# Sheet1.net
KiCad netlist of a schematic drawn in Altium Designer
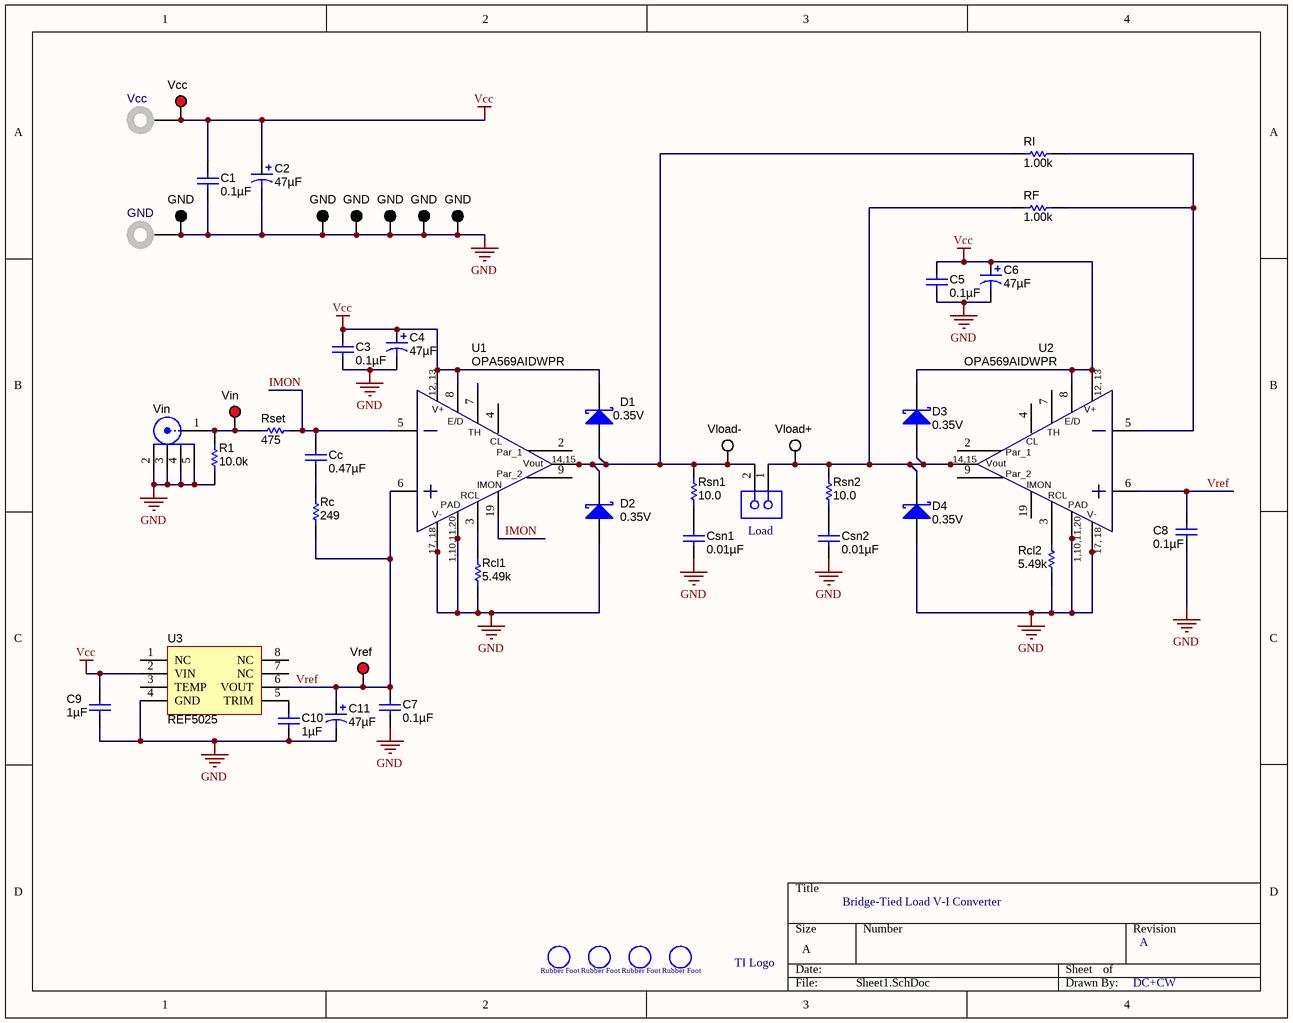
[diagram p0: Sheet1.SchDoc]

(export (version "E")
  (design (tool "Eeschema 10.0.6"))
  (components
    (comp (ref "C1")
      (value "12065C104JAT2A")
      (footprint "1206")
      (description "CAP, CERM, 0.1uF, 50V, +/-5%, X7R, 1206")
      (fields
        (field (name "VALUEDISPLAYED") "0.1µF")
        (field (name "MANUFACTURER") "AVX")
        (field (name "PUBLISHER") "Texas Instruments")
      )
      (libsource (lib "Capacitor_Ceramic") (part "12065C104JAT2A"))
    )
    (comp (ref "C2")
      (value "293D476X0016D2TE3")
      (footprint "7343-31")
      (description "CAP, TANT, 47uF, 16V, +/-20%, 0.7 ohm, 7343-31 SMD")
      (fields
        (field (name "VALUEDISPLAYED") "47µF")
        (field (name "MANUFACTURER") "Vishay-Sprague")
        (field (name "PUBLISHER") "Texas Instruments")
      )
      (libsource (lib "Capacitor_Tantalum") (part "293D476X0016D2TE3"))
    )
    (comp (ref "C3")
      (value "12065C104JAT2A")
      (footprint "1206")
      (description "CAP, CERM, 0.1uF, 50V, +/-5%, X7R, 1206")
      (fields
        (field (name "VALUEDISPLAYED") "0.1µF")
        (field (name "MANUFACTURER") "AVX")
        (field (name "PUBLISHER") "Texas Instruments")
      )
      (libsource (lib "Capacitor_Ceramic") (part "12065C104JAT2A"))
    )
    (comp (ref "C4")
      (value "293D476X0016D2TE3")
      (footprint "7343-31")
      (description "CAP, TANT, 47uF, 16V, +/-20%, 0.7 ohm, 7343-31 SMD")
      (fields
        (field (name "VALUEDISPLAYED") "47µF")
        (field (name "MANUFACTURER") "Vishay-Sprague")
        (field (name "PUBLISHER") "Texas Instruments")
      )
      (libsource (lib "Capacitor_Tantalum") (part "293D476X0016D2TE3"))
    )
    (comp (ref "C5")
      (value "12065C104JAT2A")
      (footprint "1206")
      (description "CAP, CERM, 0.1uF, 50V, +/-5%, X7R, 1206")
      (fields
        (field (name "VALUEDISPLAYED") "0.1µF")
        (field (name "MANUFACTURER") "AVX")
        (field (name "PUBLISHER") "Texas Instruments")
      )
      (libsource (lib "Capacitor_Ceramic") (part "12065C104JAT2A"))
    )
    (comp (ref "C6")
      (value "293D476X0016D2TE3")
      (footprint "7343-31")
      (description "CAP, TANT, 47uF, 16V, +/-20%, 0.7 ohm, 7343-31 SMD")
      (fields
        (field (name "VALUEDISPLAYED") "47µF")
        (field (name "MANUFACTURER") "Vishay-Sprague")
        (field (name "PUBLISHER") "Texas Instruments")
      )
      (libsource (lib "Capacitor_Tantalum") (part "293D476X0016D2TE3"))
    )
    (comp (ref "C7")
      (value "12065C104JAT2A")
      (footprint "1206")
      (description "CAP, CERM, 0.1uF, 50V, +/-5%, X7R, 1206")
      (fields
        (field (name "VALUEDISPLAYED") "0.1µF")
        (field (name "MANUFACTURER") "AVX")
        (field (name "PUBLISHER") "Texas Instruments")
      )
      (libsource (lib "Capacitor_Ceramic") (part "12065C104JAT2A"))
    )
    (comp (ref "C8")
      (value "12065C104JAT2A")
      (footprint "1206")
      (description "CAP, CERM, 0.1uF, 50V, +/-5%, X7R, 1206")
      (fields
        (field (name "VALUEDISPLAYED") "0.1µF")
        (field (name "MANUFACTURER") "AVX")
        (field (name "PUBLISHER") "Texas Instruments")
      )
      (libsource (lib "Capacitor_Ceramic") (part "12065C104JAT2A"))
    )
    (comp (ref "C9")
      (value "GRM188R71E105KA12D")
      (footprint "0603")
      (description "CAP, CERM, 1uF, 25V, +/-10%, X7R, 0603")
      (fields
        (field (name "VALUEDISPLAYED") "1µF")
        (field (name "MANUFACTURER") "MuRata")
        (field (name "PUBLISHER") "Texas Instruments")
      )
      (libsource (lib "Capacitor_Ceramic") (part "GRM188R71E105KA12D"))
    )
    (comp (ref "C10")
      (value "GRM188R71E105KA12D")
      (footprint "0603")
      (description "CAP, CERM, 1uF, 25V, +/-10%, X7R, 0603")
      (fields
        (field (name "VALUEDISPLAYED") "1µF")
        (field (name "MANUFACTURER") "MuRata")
        (field (name "PUBLISHER") "Texas Instruments")
      )
      (libsource (lib "Capacitor_Ceramic") (part "GRM188R71E105KA12D"))
    )
    (comp (ref "C11")
      (value "293D476X0016D2TE3")
      (footprint "7343-31")
      (description "CAP, TANT, 47uF, 16V, +/-20%, 0.7 ohm, 7343-31 SMD")
      (fields
        (field (name "VALUEDISPLAYED") "47µF")
        (field (name "MANUFACTURER") "Vishay-Sprague")
        (field (name "PUBLISHER") "Texas Instruments")
      )
      (libsource (lib "Capacitor_Tantalum") (part "293D476X0016D2TE3"))
    )
    (comp (ref "Cc")
      (value "C3216X7R2A474K")
      (footprint "1206")
      (description "CAP, CERM, 0.47uF, 100V, +/-10%, X7R, 1206")
      (fields
        (field (name "VALUEDISPLAYED") "0.47µF")
        (field (name "MANUFACTURER") "TDK")
        (field (name "PUBLISHER") "Texas Instruments")
      )
      (libsource (lib "Capacitor_Ceramic") (part "C3216X7R2A474K"))
    )
    (comp (ref "Csn1")
      (value "C0603C103J5RACTU")
      (footprint "0603")
      (description "CAP, CERM, 0.01uF, 50V, +/-5%, X7R, 0603")
      (fields
        (field (name "VALUEDISPLAYED") "0.01µF")
        (field (name "MANUFACTURER") "Kemet")
        (field (name "PUBLISHER") "Texas Instruments")
      )
      (libsource (lib "Capacitor_Ceramic") (part "C0603C103J5RACTU"))
    )
    (comp (ref "Csn2")
      (value "C0603C103J5RACTU")
      (footprint "0603")
      (description "CAP, CERM, 0.01uF, 50V, +/-5%, X7R, 0603")
      (fields
        (field (name "VALUEDISPLAYED") "0.01µF")
        (field (name "MANUFACTURER") "Kemet")
        (field (name "PUBLISHER") "Texas Instruments")
      )
      (libsource (lib "Capacitor_Ceramic") (part "C0603C103J5RACTU"))
    )
    (comp (ref "D1")
      (value "0.35V")
      (footprint "SMC")
      (description "Diode, Schottky, 15V, 3A, SMC")
      (fields
        (field (name "PARTNUMBER") "30BQ015TRPBF")
        (field (name "MANUFACTURER") "International Rectifier")
        (field (name "PUBLISHER") "Texas Instruments")
      )
      (libsource (lib "Diode") (part "30BQ015TRPBF"))
    )
    (comp (ref "D2")
      (value "0.35V")
      (footprint "SMC")
      (description "Diode, Schottky, 15V, 3A, SMC")
      (fields
        (field (name "PARTNUMBER") "30BQ015TRPBF")
        (field (name "MANUFACTURER") "International Rectifier")
        (field (name "PUBLISHER") "Texas Instruments")
      )
      (libsource (lib "Diode") (part "30BQ015TRPBF"))
    )
    (comp (ref "D3")
      (value "0.35V")
      (footprint "SMC")
      (description "Diode, Schottky, 15V, 3A, SMC")
      (fields
        (field (name "PARTNUMBER") "30BQ015TRPBF")
        (field (name "MANUFACTURER") "International Rectifier")
        (field (name "PUBLISHER") "Texas Instruments")
      )
      (libsource (lib "Diode") (part "30BQ015TRPBF"))
    )
    (comp (ref "D4")
      (value "0.35V")
      (footprint "SMC")
      (description "Diode, Schottky, 15V, 3A, SMC")
      (fields
        (field (name "PARTNUMBER") "30BQ015TRPBF")
        (field (name "MANUFACTURER") "International Rectifier")
        (field (name "PUBLISHER") "Texas Instruments")
      )
      (libsource (lib "Diode") (part "30BQ015TRPBF"))
    )
    (comp (ref "F1")
      (value "~")
      (footprint "Rubber_Foot")
      (description "BUMPON CYLINDRICAL .312X.200 BLK")
      (fields (field (name "MANUFACTURER") "3M") (field (name "SYMBOLCREATOR") "use LDAP id"))
      (libsource (lib "Schlib1") (part "SJ61A1"))
    )
    (comp (ref "F2")
      (value "~")
      (footprint "Rubber_Foot")
      (description "BUMPON CYLINDRICAL .312X.200 BLK")
      (fields (field (name "MANUFACTURER") "3M") (field (name "SYMBOLCREATOR") "use LDAP id"))
      (libsource (lib "Schlib1") (part "SJ61A1"))
    )
    (comp (ref "F3")
      (value "~")
      (footprint "Rubber_Foot")
      (description "BUMPON CYLINDRICAL .312X.200 BLK")
      (fields (field (name "MANUFACTURER") "3M") (field (name "SYMBOLCREATOR") "use LDAP id"))
      (libsource (lib "Schlib1") (part "SJ61A1"))
    )
    (comp (ref "F4")
      (value "~")
      (footprint "Rubber_Foot")
      (description "BUMPON CYLINDRICAL .312X.200 BLK")
      (fields (field (name "MANUFACTURER") "3M") (field (name "SYMBOLCREATOR") "use LDAP id"))
      (libsource (lib "Schlib1") (part "SJ61A1"))
    )
    (comp (ref "GND")
      (value "~")
      (footprint "Keystone_575-4")
      (description "Standard Banana Jack, Uninsulated, 5.5mm")
      (fields
        (field (name "PARTNUMBER") "575-4")
        (field (name "MANUFACTURER") "Keystone")
        (field (name "PUBLISHER") "National Semiconductor")
      )
      (libsource (lib "Connectors") (part "575-4"))
    )
    (comp (ref "Load")
      (value "~")
      (footprint "PhoenixContact_1715721")
      (description "Conn Term Block, 2POS, 5.08mm PCB")
      (fields
        (field (name "PARTNUMBER") "1715721")
        (field (name "MANUFACTURER") "Phoenix Contact")
        (field (name "PUBLISHER") "National Semiconductor")
      )
      (libsource (lib "Connectors") (part "1715721"))
    )
    (comp (ref "R1")
      (value "10.0k")
      (footprint "0603")
      (description "RES, 10.0k ohm, 1%, 0.1W, 0603")
      (fields
        (field (name "PARTNUMBER") "RC0603FR-0710KL")
        (field (name "MANUFACTURER") "Yageo America")
        (field (name "PUBLISHER") "Texas Instruments")
      )
      (libsource (lib "Resistor_0603") (part "RC0603FR-0710KL"))
    )
    (comp (ref "Rc")
      (value "249")
      (footprint "0603")
      (description "RES, 249 ohm, 1%, 0.1W, 0603")
      (fields
        (field (name "PARTNUMBER") "RC0603FR-07249RL")
        (field (name "MANUFACTURER") "Yageo America")
        (field (name "PUBLISHER") "Texas Instruments")
      )
      (libsource (lib "Resistor_0603") (part "RC0603FR-07249RL"))
    )
    (comp (ref "Rcl1")
      (value "5.49k")
      (footprint "0603")
      (description "RES, 5.49k ohm, 1%, 0.1W, 0603")
      (fields
        (field (name "PARTNUMBER") "RC0603FR-075K49L")
        (field (name "MANUFACTURER") "Yageo America")
        (field (name "PUBLISHER") "Texas Instruments")
      )
      (libsource (lib "Resistor_0603") (part "RC0603FR-075K49L"))
    )
    (comp (ref "Rcl2")
      (value "5.49k")
      (footprint "0603")
      (description "RES, 5.49k ohm, 1%, 0.1W, 0603")
      (fields
        (field (name "PARTNUMBER") "RC0603FR-075K49L")
        (field (name "MANUFACTURER") "Yageo America")
        (field (name "PUBLISHER") "Texas Instruments")
      )
      (libsource (lib "Resistor_0603") (part "RC0603FR-075K49L"))
    )
    (comp (ref "RF")
      (value "1.00k")
      (footprint "0603")
      (description "RES, 1.00k ohm, 1%, 0.1W, 0603")
      (fields
        (field (name "PARTNUMBER") "RC0603FR-071KL")
        (field (name "MANUFACTURER") "Yageo America")
        (field (name "PUBLISHER") "Texas Instruments")
      )
      (libsource (lib "Resistor_0603") (part "RC0603FR-071KL"))
    )
    (comp (ref "RI")
      (value "1.00k")
      (footprint "0603")
      (description "RES, 1.00k ohm, 1%, 0.1W, 0603")
      (fields
        (field (name "PARTNUMBER") "RC0603FR-071KL")
        (field (name "MANUFACTURER") "Yageo America")
        (field (name "PUBLISHER") "Texas Instruments")
      )
      (libsource (lib "Resistor_0603") (part "RC0603FR-071KL"))
    )
    (comp (ref "Rset")
      (value "475")
      (footprint "0603")
      (description "RES, 475 ohm, 1%, 0.1W, 0603")
      (fields
        (field (name "PARTNUMBER") "RC0603FR-07475RL")
        (field (name "MANUFACTURER") "Yageo America")
        (field (name "PUBLISHER") "Texas Instruments")
      )
      (libsource (lib "Resistor_0603") (part "RC0603FR-07475RL"))
    )
    (comp (ref "Rsn1")
      (value "10.0")
      (footprint "0603")
      (description "RES, 10.0 ohm, 1%, 0.1W, 0603")
      (fields
        (field (name "PARTNUMBER") "CRCW060310R0FKEA")
        (field (name "MANUFACTURER") "Vishay-Dale")
        (field (name "PUBLISHER") "Texas Instruments")
      )
      (libsource (lib "Resistor_0603") (part "CRCW060310R0FKEA"))
    )
    (comp (ref "Rsn2")
      (value "10.0")
      (footprint "0603")
      (description "RES, 10.0 ohm, 1%, 0.1W, 0603")
      (fields
        (field (name "PARTNUMBER") "CRCW060310R0FKEA")
        (field (name "MANUFACTURER") "Vishay-Dale")
        (field (name "PUBLISHER") "Texas Instruments")
      )
      (libsource (lib "Resistor_0603") (part "CRCW060310R0FKEA"))
    )
    (comp (ref "TI1")
      (value "Texas Instruments logo")
      (footprint "TI LOGO")
      (description "TI BUG")
      (libsource (lib "Schlib1") (part "TI LOGO"))
    )
    (comp (ref "TP1")
      (value "Vcc")
      (footprint "Keystone5000")
      (description "Test Point, TH, Miniature, Red")
      (fields
        (field (name "MANUFACTURER") "Keystone")
        (field (name "DIGIKEYPARTNUMBER") "5000K-ND")
        (field (name "PUBLISHER") "National Semiconductor")
      )
      (libsource (lib "Connectors") (part "5000"))
    )
    (comp (ref "TP2")
      (value "GND")
      (footprint "Keystone5001")
      (description "Test Point, TH, Miniature, Black")
      (fields
        (field (name "MANUFACTURER") "Keystone")
        (field (name "DIGIKEYPARTNUMBER") "5001K-ND")
        (field (name "PUBLISHER") "National Semiconductor")
      )
      (libsource (lib "Connectors") (part "5001"))
    )
    (comp (ref "TP3")
      (value "GND")
      (footprint "Keystone5001")
      (description "Test Point, TH, Miniature, Black")
      (fields
        (field (name "MANUFACTURER") "Keystone")
        (field (name "DIGIKEYPARTNUMBER") "5001K-ND")
        (field (name "PUBLISHER") "National Semiconductor")
      )
      (libsource (lib "Connectors") (part "5001"))
    )
    (comp (ref "TP4")
      (value "GND")
      (footprint "Keystone5001")
      (description "Test Point, TH, Miniature, Black")
      (fields
        (field (name "MANUFACTURER") "Keystone")
        (field (name "DIGIKEYPARTNUMBER") "5001K-ND")
        (field (name "PUBLISHER") "National Semiconductor")
      )
      (libsource (lib "Connectors") (part "5001"))
    )
    (comp (ref "TP5")
      (value "GND")
      (footprint "Keystone5001")
      (description "Test Point, TH, Miniature, Black")
      (fields
        (field (name "MANUFACTURER") "Keystone")
        (field (name "DIGIKEYPARTNUMBER") "5001K-ND")
        (field (name "PUBLISHER") "National Semiconductor")
      )
      (libsource (lib "Connectors") (part "5001"))
    )
    (comp (ref "TP6")
      (value "GND")
      (footprint "Keystone5001")
      (description "Test Point, TH, Miniature, Black")
      (fields
        (field (name "MANUFACTURER") "Keystone")
        (field (name "DIGIKEYPARTNUMBER") "5001K-ND")
        (field (name "PUBLISHER") "National Semiconductor")
      )
      (libsource (lib "Connectors") (part "5001"))
    )
    (comp (ref "TP7")
      (value "GND")
      (footprint "Keystone5001")
      (description "Test Point, TH, Miniature, Black")
      (fields
        (field (name "MANUFACTURER") "Keystone")
        (field (name "DIGIKEYPARTNUMBER") "5001K-ND")
        (field (name "PUBLISHER") "National Semiconductor")
      )
      (libsource (lib "Connectors") (part "5001"))
    )
    (comp (ref "TP9")
      (value "Vin")
      (footprint "Keystone5000")
      (description "Test Point, TH, Miniature, Red")
      (fields
        (field (name "MANUFACTURER") "Keystone")
        (field (name "DIGIKEYPARTNUMBER") "5000K-ND")
        (field (name "PUBLISHER") "National Semiconductor")
      )
      (libsource (lib "Connectors") (part "5000"))
    )
    (comp (ref "TP10")
      (value "Vload-")
      (footprint "Keystone5002")
      (description "Test Point, TH, Miniature, White")
      (fields
        (field (name "MANUFACTURER") "Keystone")
        (field (name "DIGIKEYPARTNUMBER") "5002K-ND")
        (field (name "PUBLISHER") "National Semiconductor")
      )
      (libsource (lib "Connectors") (part "5002"))
    )
    (comp (ref "TP11")
      (value "Vload+")
      (footprint "Keystone5002")
      (description "Test Point, TH, Miniature, White")
      (fields
        (field (name "MANUFACTURER") "Keystone")
        (field (name "DIGIKEYPARTNUMBER") "5002K-ND")
        (field (name "PUBLISHER") "National Semiconductor")
      )
      (libsource (lib "Connectors") (part "5002"))
    )
    (comp (ref "TP13")
      (value "Vref")
      (footprint "Keystone5000")
      (description "Test Point, TH, Miniature, Red")
      (fields
        (field (name "MANUFACTURER") "Keystone")
        (field (name "DIGIKEYPARTNUMBER") "5000K-ND")
        (field (name "PUBLISHER") "National Semiconductor")
      )
      (libsource (lib "Connectors") (part "5000"))
    )
    (comp (ref "U1")
      (value "OPA569AIDWPR")
      (footprint "SOIC-20-PWP (DWP)")
      (description "IC OPAMP GP R-R 1.2MHZ 20SOIC")
      (fields (field (name "MANUFACTURER") "Texas Instruments") (field (name "SYMBOLCREATOR") "Use LDAP id"))
      (libsource (lib "Schlib1") (part "OPA569"))
    )
    (comp (ref "U2")
      (value "OPA569AIDWPR")
      (footprint "SOIC-20-PWP (DWP)")
      (description "IC OPAMP GP R-R 1.2MHZ 20SOIC")
      (fields (field (name "MANUFACTURER") "Texas Instruments") (field (name "SYMBOLCREATOR") "Use LDAP id"))
      (libsource (lib "Schlib1") (part "OPA569"))
    )
    (comp (ref "U3")
      (value "REF5025")
      (footprint "M08A_M")
      (description "IC VREF SERIES PREC 2.5V 8-SOIC")
      (fields
        (field (name "MANUFACTURER") "Texas Instruments")
        (field (name "PARTNUMBER") "8-SOIC")
        (field (name "SYMBOLCREATOR") "Use LDAP id")
      )
      (libsource (lib "Schlib1") (part "REF5025"))
    )
    (comp (ref "Vcc")
      (value "~")
      (footprint "Keystone_575-4")
      (description "Standard Banana Jack, Uninsulated, 5.5mm")
      (fields
        (field (name "PARTNUMBER") "575-4")
        (field (name "MANUFACTURER") "Keystone")
        (field (name "PUBLISHER") "National Semiconductor")
      )
      (libsource (lib "Connectors") (part "575-4"))
    )
    (comp (ref "Vin")
      (value "~")
      (footprint "Johnson_142-0701-20x")
      (description "Connector, TH, SMA")
      (fields
        (field (name "PARTNUMBER") "142-0701-201")
        (field (name "MANUFACTURER") "Emerson Network Power")
        (field (name "PUBLISHER") "National Semiconductor")
      )
      (libsource (lib "Connectors") (part "142-0701-201"))
    )
  )
  (nets
    (net (code "1") (name "/IMON") (class "Default")
      (node (ref "Cc") (pin "1") (pinfunction "1_1") (pintype "passive"))
      (node (ref "Rset") (pin "2") (pinfunction "2_2") (pintype "passive"))
      (node (ref "U1") (pin "19") (pinfunction "Imon_19") (pintype "passive"))
      (node (ref "U1") (pin "5") (pinfunction "IN-_5") (pintype "passive"))
    )
    (net (code "2") (name "/Vref") (class "Default")
      (node (ref "C11") (pin "1") (pinfunction "+_1") (pintype "passive"))
      (node (ref "C7") (pin "1") (pinfunction "1_1") (pintype "passive"))
      (node (ref "C8") (pin "1") (pinfunction "1_1") (pintype "passive"))
      (node (ref "Rc") (pin "1") (pinfunction "1_1") (pintype "passive"))
      (node (ref "TP13") (pin "1") (pintype "passive"))
      (node (ref "U1") (pin "6") (pinfunction "IN+_6") (pintype "passive"))
      (node (ref "U2") (pin "6") (pinfunction "IN+_6") (pintype "passive"))
      (node (ref "U3") (pin "6") (pinfunction "VOUT_6") (pintype "passive"))
    )
    (net (code "3") (name "GND") (class "Default")
      (node (ref "C1") (pin "2") (pinfunction "2_2") (pintype "passive"))
      (node (ref "C10") (pin "2") (pinfunction "2_2") (pintype "passive"))
      (node (ref "C11") (pin "2") (pinfunction "-_2") (pintype "passive"))
      (node (ref "C2") (pin "2") (pinfunction "-_2") (pintype "passive"))
      (node (ref "C3") (pin "2") (pinfunction "2_2") (pintype "passive"))
      (node (ref "C4") (pin "2") (pinfunction "-_2") (pintype "passive"))
      (node (ref "C5") (pin "2") (pinfunction "2_2") (pintype "passive"))
      (node (ref "C6") (pin "2") (pinfunction "-_2") (pintype "passive"))
      (node (ref "C7") (pin "2") (pinfunction "2_2") (pintype "passive"))
      (node (ref "C8") (pin "2") (pinfunction "2_2") (pintype "passive"))
      (node (ref "C9") (pin "2") (pinfunction "2_2") (pintype "passive"))
      (node (ref "Csn1") (pin "2") (pinfunction "2_2") (pintype "passive"))
      (node (ref "Csn2") (pin "2") (pinfunction "2_2") (pintype "passive"))
      (node (ref "D2") (pin "2") (pinfunction "A_2") (pintype "passive"))
      (node (ref "D4") (pin "2") (pinfunction "A_2") (pintype "passive"))
      (node (ref "GND") (pin "1") (pinfunction "1_1") (pintype "passive"))
      (node (ref "R1") (pin "1") (pinfunction "1_1") (pintype "passive"))
      (node (ref "Rcl1") (pin "1") (pinfunction "1_1") (pintype "passive"))
      (node (ref "Rcl2") (pin "1") (pinfunction "1_1") (pintype "passive"))
      (node (ref "TP2") (pin "1") (pintype "passive"))
      (node (ref "TP3") (pin "1") (pintype "passive"))
      (node (ref "TP4") (pin "1") (pintype "passive"))
      (node (ref "TP5") (pin "1") (pintype "passive"))
      (node (ref "TP6") (pin "1") (pintype "passive"))
      (node (ref "TP7") (pin "1") (pintype "passive"))
      (node (ref "U1") (pin "1") (pinfunction "PAD_1") (pintype "passive"))
      (node (ref "U1") (pin "10") (pinfunction "PAD_10") (pintype "passive"))
      (node (ref "U1") (pin "11") (pinfunction "PAD_11") (pintype "passive"))
      (node (ref "U1") (pin "17") (pinfunction "V-_17") (pintype "passive"))
      (node (ref "U1") (pin "18") (pinfunction "V-_18") (pintype "passive"))
      (node (ref "U1") (pin "20") (pinfunction "PAD_20") (pintype "passive"))
      (node (ref "U1") (pin "21") (pinfunction "PAD_21") (pintype "passive"))
      (node (ref "U2") (pin "1") (pinfunction "PAD_1") (pintype "passive"))
      (node (ref "U2") (pin "10") (pinfunction "PAD_10") (pintype "passive"))
      (node (ref "U2") (pin "11") (pinfunction "PAD_11") (pintype "passive"))
      (node (ref "U2") (pin "17") (pinfunction "V-_17") (pintype "passive"))
      (node (ref "U2") (pin "18") (pinfunction "V-_18") (pintype "passive"))
      (node (ref "U2") (pin "20") (pinfunction "PAD_20") (pintype "passive"))
      (node (ref "U2") (pin "21") (pinfunction "PAD_21") (pintype "passive"))
      (node (ref "U3") (pin "4") (pinfunction "GND_4") (pintype "passive"))
      (node (ref "Vin") (pin "2") (pinfunction "2_2") (pintype "passive"))
      (node (ref "Vin") (pin "3") (pinfunction "3_3") (pintype "passive"))
      (node (ref "Vin") (pin "4") (pinfunction "4_4") (pintype "passive"))
      (node (ref "Vin") (pin "5") (pinfunction "5_5") (pintype "passive"))
    )
    (net (code "4") (name "Net-(Cc-Pad2)") (class "Default")
      (node (ref "Cc") (pin "2") (pinfunction "2_2") (pintype "passive"))
      (node (ref "Rc") (pin "2") (pinfunction "2_2") (pintype "passive"))
    )
    (net (code "5") (name "Net-(Csn1-Pad1)") (class "Default")
      (node (ref "Csn1") (pin "1") (pinfunction "1_1") (pintype "passive"))
      (node (ref "Rsn1") (pin "1") (pinfunction "1_1") (pintype "passive"))
    )
    (net (code "6") (name "Net-(Csn2-Pad1)") (class "Default")
      (node (ref "Csn2") (pin "1") (pinfunction "1_1") (pintype "passive"))
      (node (ref "Rsn2") (pin "1") (pinfunction "1_1") (pintype "passive"))
    )
    (net (code "7") (name "Net-(D1-A)") (class "Default")
      (node (ref "D1") (pin "2") (pinfunction "A_2") (pintype "passive"))
      (node (ref "D2") (pin "1") (pinfunction "K_1") (pintype "passive"))
      (node (ref "Load") (pin "2") (pinfunction "2_2") (pintype "passive"))
      (node (ref "RI") (pin "2") (pinfunction "2_2") (pintype "passive"))
      (node (ref "Rsn1") (pin "2") (pinfunction "2_2") (pintype "passive"))
      (node (ref "TP10") (pin "1") (pintype "passive"))
      (node (ref "U1") (pin "14") (pinfunction "Vo_14") (pintype "passive"))
      (node (ref "U1") (pin "15") (pinfunction "Vo_15") (pintype "passive"))
    )
    (net (code "8") (name "Net-(D3-A)") (class "Default")
      (node (ref "D3") (pin "2") (pinfunction "A_2") (pintype "passive"))
      (node (ref "D4") (pin "1") (pinfunction "K_1") (pintype "passive"))
      (node (ref "Load") (pin "1") (pinfunction "1_1") (pintype "passive"))
      (node (ref "RF") (pin "2") (pinfunction "2_2") (pintype "passive"))
      (node (ref "Rsn2") (pin "2") (pinfunction "2_2") (pintype "passive"))
      (node (ref "TP11") (pin "1") (pintype "passive"))
      (node (ref "U2") (pin "14") (pinfunction "Vo_14") (pintype "passive"))
      (node (ref "U2") (pin "15") (pinfunction "Vo_15") (pintype "passive"))
    )
    (net (code "9") (name "Net-(R1-Pad2)") (class "Default")
      (node (ref "R1") (pin "2") (pinfunction "2_2") (pintype "passive"))
      (node (ref "Rset") (pin "1") (pinfunction "1_1") (pintype "passive"))
      (node (ref "TP9") (pin "1") (pintype "passive"))
      (node (ref "Vin") (pin "1") (pinfunction "1_1") (pintype "passive"))
    )
    (net (code "10") (name "Net-(U1-RCL)") (class "Default")
      (node (ref "Rcl1") (pin "2") (pinfunction "2_2") (pintype "passive"))
      (node (ref "U1") (pin "3") (pinfunction "RCL_3") (pintype "passive"))
    )
    (net (code "11") (name "Net-(U2-IN-)") (class "Default")
      (node (ref "RF") (pin "1") (pinfunction "1_1") (pintype "passive"))
      (node (ref "RI") (pin "1") (pinfunction "1_1") (pintype "passive"))
      (node (ref "U2") (pin "5") (pinfunction "IN-_5") (pintype "passive"))
    )
    (net (code "12") (name "Net-(U2-RCL)") (class "Default")
      (node (ref "Rcl2") (pin "2") (pinfunction "2_2") (pintype "passive"))
      (node (ref "U2") (pin "3") (pinfunction "RCL_3") (pintype "passive"))
    )
    (net (code "13") (name "Net-(U3-TRIM)") (class "Default")
      (node (ref "C10") (pin "1") (pinfunction "1_1") (pintype "passive"))
      (node (ref "U3") (pin "5") (pinfunction "TRIM_5") (pintype "passive"))
    )
    (net (code "14") (name "Vcc") (class "Default")
      (node (ref "C1") (pin "1") (pinfunction "1_1") (pintype "passive"))
      (node (ref "C2") (pin "1") (pinfunction "+_1") (pintype "passive"))
      (node (ref "C3") (pin "1") (pinfunction "1_1") (pintype "passive"))
      (node (ref "C4") (pin "1") (pinfunction "+_1") (pintype "passive"))
      (node (ref "C5") (pin "1") (pinfunction "1_1") (pintype "passive"))
      (node (ref "C6") (pin "1") (pinfunction "+_1") (pintype "passive"))
      (node (ref "C9") (pin "1") (pinfunction "1_1") (pintype "passive"))
      (node (ref "D1") (pin "1") (pinfunction "K_1") (pintype "passive"))
      (node (ref "D3") (pin "1") (pinfunction "K_1") (pintype "passive"))
      (node (ref "TP1") (pin "1") (pintype "passive"))
      (node (ref "U1") (pin "12") (pinfunction "V+_12") (pintype "passive"))
      (node (ref "U1") (pin "13") (pinfunction "V+_13") (pintype "passive"))
      (node (ref "U1") (pin "8") (pinfunction "E/~{D}_8") (pintype "passive"))
      (node (ref "U2") (pin "12") (pinfunction "V+_12") (pintype "passive"))
      (node (ref "U2") (pin "13") (pinfunction "V+_13") (pintype "passive"))
      (node (ref "U2") (pin "8") (pinfunction "E/~{D}_8") (pintype "passive"))
      (node (ref "U3") (pin "2") (pinfunction "VIN_2") (pintype "passive"))
      (node (ref "Vcc") (pin "1") (pinfunction "1_1") (pintype "passive"))
    )
    (net (code "15") (name "unconnected-(U1-CL-Pad4)") (class "Default")
      (node (ref "U1") (pin "4") (pinfunction "CL_4") (pintype "passive"))
    )
    (net (code "16") (name "unconnected-(U1-NC-Pad16)") (class "Default")
      (node (ref "U1") (pin "16") (pinfunction "NC_16") (pintype "passive"))
    )
    (net (code "17") (name "unconnected-(U1-Par_1-Pad2)") (class "Default")
      (node (ref "U1") (pin "2") (pinfunction "Par_1_2") (pintype "passive"))
    )
    (net (code "18") (name "unconnected-(U1-Par_2-Pad9)") (class "Default")
      (node (ref "U1") (pin "9") (pinfunction "Par_2_9") (pintype "passive"))
    )
    (net (code "19") (name "unconnected-(U1-TH-Pad7)") (class "Default")
      (node (ref "U1") (pin "7") (pinfunction "TH_7") (pintype "passive"))
    )
    (net (code "20") (name "unconnected-(U2-CL-Pad4)") (class "Default")
      (node (ref "U2") (pin "4") (pinfunction "CL_4") (pintype "passive"))
    )
    (net (code "21") (name "unconnected-(U2-Imon-Pad19)") (class "Default")
      (node (ref "U2") (pin "19") (pinfunction "Imon_19") (pintype "passive"))
    )
    (net (code "22") (name "unconnected-(U2-NC-Pad16)") (class "Default")
      (node (ref "U2") (pin "16") (pinfunction "NC_16") (pintype "passive"))
    )
    (net (code "23") (name "unconnected-(U2-Par_1-Pad2)") (class "Default")
      (node (ref "U2") (pin "2") (pinfunction "Par_1_2") (pintype "passive"))
    )
    (net (code "24") (name "unconnected-(U2-Par_2-Pad9)") (class "Default")
      (node (ref "U2") (pin "9") (pinfunction "Par_2_9") (pintype "passive"))
    )
    (net (code "25") (name "unconnected-(U2-TH-Pad7)") (class "Default")
      (node (ref "U2") (pin "7") (pinfunction "TH_7") (pintype "passive"))
    )
    (net (code "26") (name "unconnected-(U3-NC-Pad1)") (class "Default")
      (node (ref "U3") (pin "1") (pinfunction "NC_1") (pintype "passive"))
    )
    (net (code "27") (name "unconnected-(U3-NC-Pad7)") (class "Default")
      (node (ref "U3") (pin "7") (pinfunction "NC_7") (pintype "passive"))
    )
    (net (code "28") (name "unconnected-(U3-NC-Pad8)") (class "Default")
      (node (ref "U3") (pin "8") (pinfunction "NC_8") (pintype "passive"))
    )
    (net (code "29") (name "unconnected-(U3-TEMP-Pad3)") (class "Default")
      (node (ref "U3") (pin "3") (pinfunction "TEMP_3") (pintype "passive"))
    )
  )
)
